# openSX70_ALPHA_V6_5-20181015.net
KiCad netlist of a schematic drawn in EAGLE
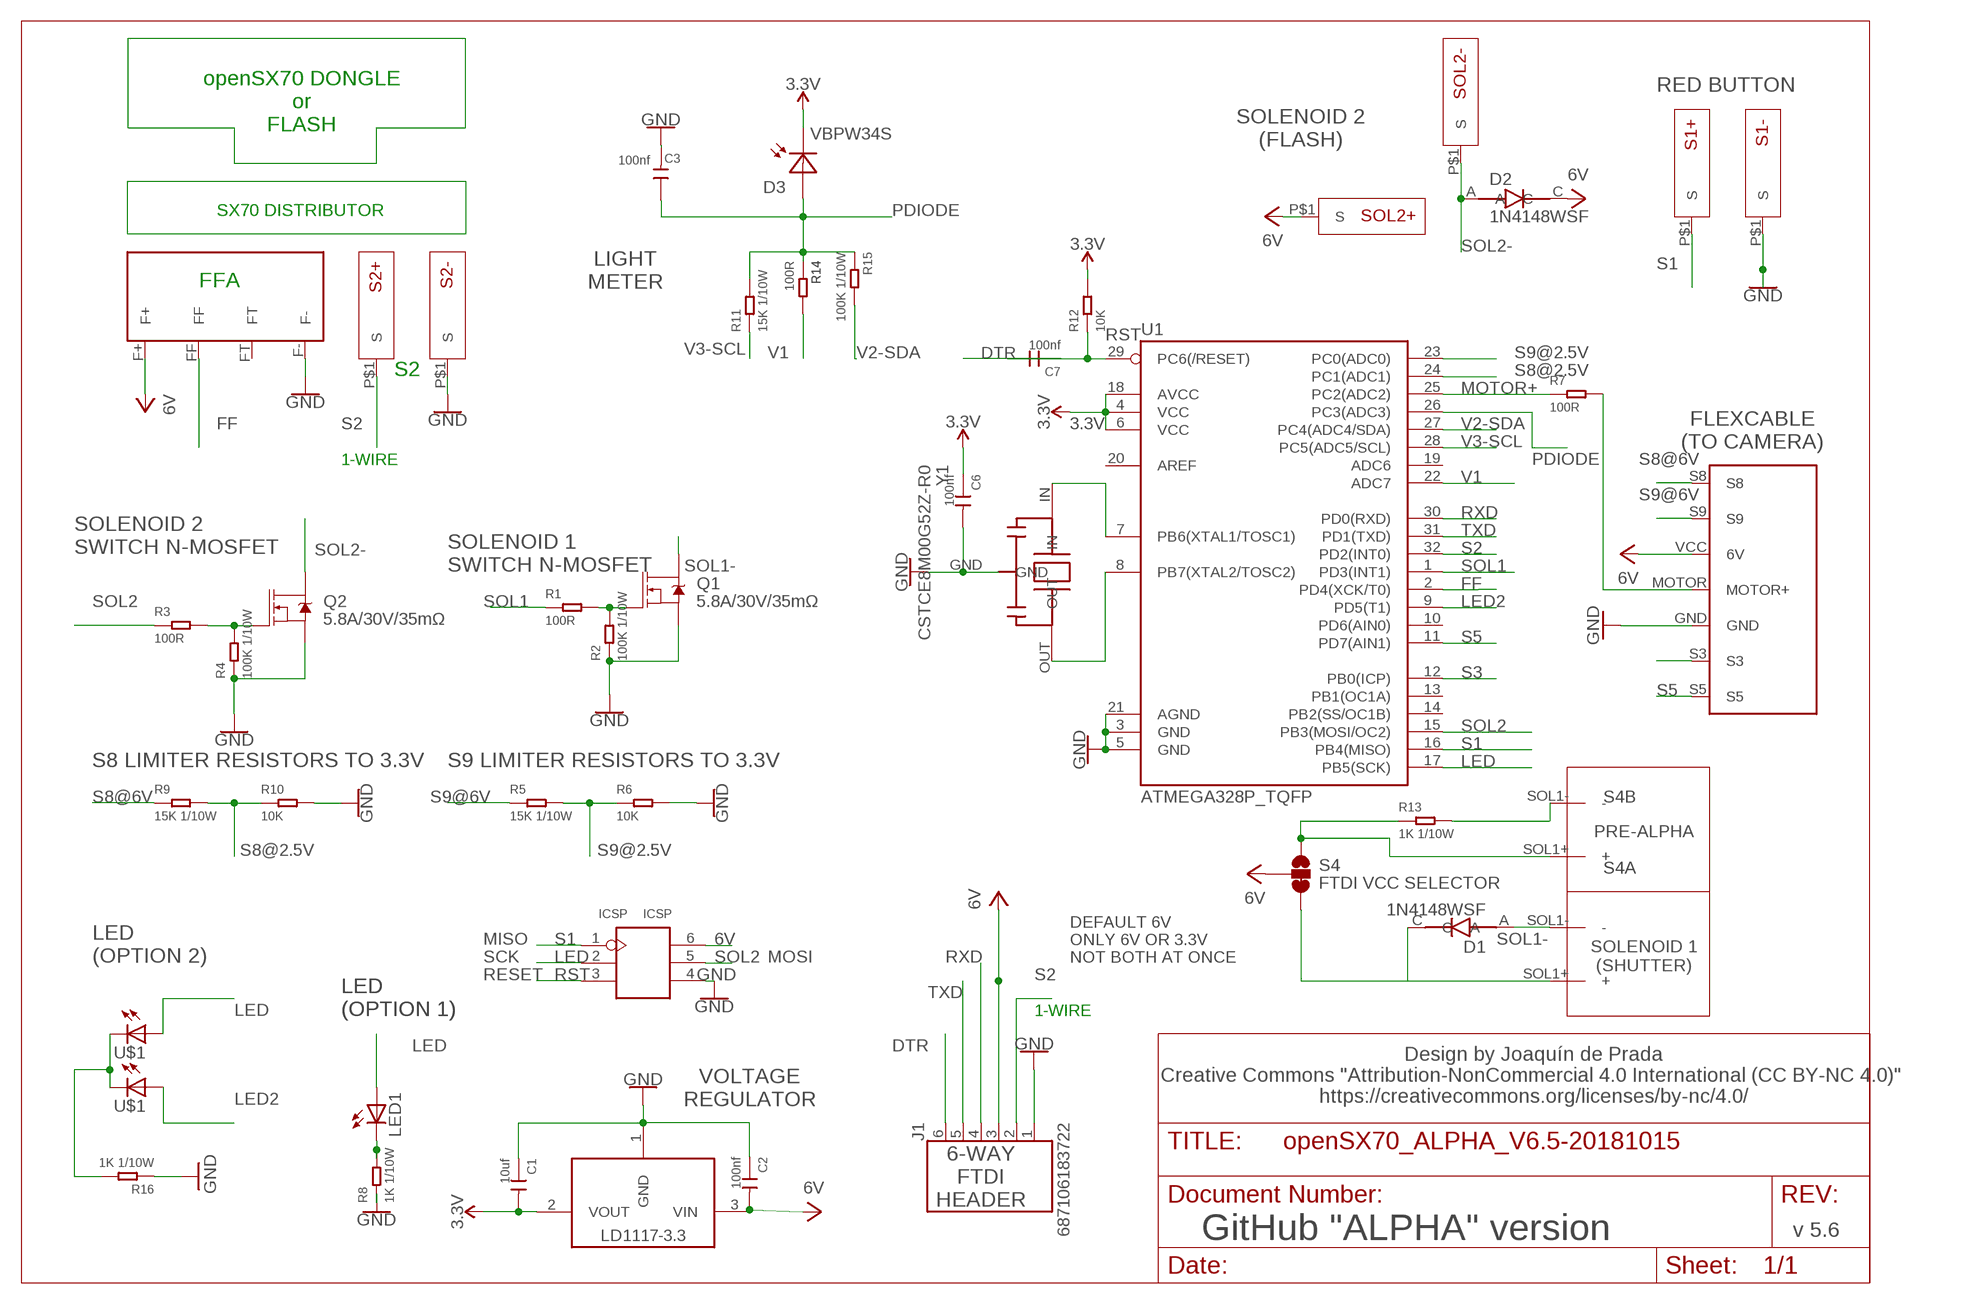
[diagram p0: schematic, sheet 1]

(export (version "E")
  (design (tool "Eeschema 10.0.6"))
  (components
    (comp (ref "C1")
      (value "10uf")
      (footprint "eagle-import:C0603")
      (fields (field (name "MPN") "CC0603KRX5R6BB106"))
      (libsource (lib "eagle-import") (part "CERAMIC-10UF-10V-10%-X5R(0603)"))
    )
    (comp (ref "C2")
      (value "100nf")
      (footprint "eagle-import:C0603")
      (fields (field (name "MPN") "CC0603KRX7R9BB104"))
      (libsource (lib "eagle-import") (part "CERAMIC-100NF-50V-10%-X7R(0603)"))
    )
    (comp (ref "C3")
      (value "100nf")
      (footprint "eagle-import:C0603")
      (fields (field (name "MPN") "CC0603KRX7R9BB104"))
      (libsource (lib "eagle-import") (part "CERAMIC-100NF-50V-10%-X7R(0603)"))
    )
    (comp (ref "C6")
      (value "100nf")
      (footprint "eagle-import:C0603")
      (fields (field (name "MPN") "CC0603KRX7R9BB104"))
      (libsource (lib "eagle-import") (part "CERAMIC-100NF-50V-10%-X7R(0603)"))
    )
    (comp (ref "C7")
      (value "100nf")
      (footprint "eagle-import:C0603")
      (fields (field (name "MPN") "CC0603KRX7R9BB104"))
      (libsource (lib "eagle-import") (part "CERAMIC-100NF-50V-10%-X7R(0603)"))
    )
    (comp (ref "D1")
      (value "1N4148WSF")
      (footprint "eagle-import:SODFL2512X100N")
      (fields (field (name "MANUFACTURER") "Fairchild Semiconductor"))
      (libsource (lib "eagle-import") (part "1N4148WS"))
    )
    (comp (ref "D2")
      (value "1N4148WSF")
      (footprint "eagle-import:SODFL2512X100N")
      (fields (field (name "MANUFACTURER") "Fairchild Semiconductor"))
      (libsource (lib "eagle-import") (part "1N4148WS"))
    )
    (comp (ref "D3")
      (value "VBPW34S")
      (footprint "eagle-import:SOD6439X130N")
      (fields (field (name "DIGI-KEY_PART_NUMBER") "751-1500-1-ND") (field (name "MF") "Vishay"))
      (libsource (lib "eagle-import") (part "VBPW34S"))
    )
    (comp (ref "ICSP")
      (value "ICSP")
      (footprint "eagle-import:H2X3-2.54")
      (libsource (lib "eagle-import") (part "ICSP"))
    )
    (comp (ref "J1")
      (value "687106183722")
      (footprint "eagle-import:687106183722")
      (fields (field (name "MF") "Wurth Electronics"))
      (libsource (lib "eagle-import") (part "687106183722"))
    )
    (comp (ref "LD11172.5V")
      (value "LD1117 2.5V")
      (footprint "eagle-import:SOT223")
      (fields (field (name "MF") "Advanced Monolithic Systems") (field (name "MP") "AMS1117-5.0"))
      (libsource (lib "eagle-import") (part "LD1117-3.3"))
    )
    (comp (ref "LED1")
      (value "LEDCHIPLED_0805")
      (footprint "eagle-import:CHIPLED_0805")
      (libsource (lib "eagle-import") (part "LEDCHIPLED_0805"))
    )
    (comp (ref "Q1")
      (value "5.8A/30V/35mΩ")
      (footprint "eagle-import:SOT23-3")
      (libsource (lib "eagle-import") (part "MOSFET-NCH-AO3404A"))
    )
    (comp (ref "Q2")
      (value "5.8A/30V/35mΩ")
      (footprint "eagle-import:SOT23-3")
      (libsource (lib "eagle-import") (part "MOSFET-NCH-AO3404A"))
    )
    (comp (ref "R1")
      (value "100R")
      (footprint "eagle-import:R0603")
      (fields (field (name "MPN") "RC0603JR-07100RL"))
      (libsource (lib "eagle-import") (part "SMD-RES-100R-5%-1/10W(0603)"))
    )
    (comp (ref "R2")
      (value "100K 1/10W")
      (footprint "eagle-import:R0603")
      (fields (field (name "MPN") "RC0603JR-07100KL"))
      (libsource (lib "eagle-import") (part "SMD-RES-100K-5%-1/10W(0603)"))
    )
    (comp (ref "R3")
      (value "100R")
      (footprint "eagle-import:R0603")
      (fields (field (name "MPN") "RC0603JR-07100RL"))
      (libsource (lib "eagle-import") (part "SMD-RES-100R-5%-1/10W(0603)"))
    )
    (comp (ref "R4")
      (value "100K 1/10W")
      (footprint "eagle-import:R0603")
      (fields (field (name "MPN") "RC0603JR-07100KL"))
      (libsource (lib "eagle-import") (part "SMD-RES-100K-5%-1/10W(0603)"))
    )
    (comp (ref "R5")
      (value "15K 1/10W")
      (footprint "eagle-import:R0603")
      (fields (field (name "MPN") "RC0603FR-0715KL"))
      (libsource (lib "eagle-import") (part "SMD-RES-15K-1%-1/10W(0603)"))
    )
    (comp (ref "R6")
      (value "10K")
      (footprint "eagle-import:R0603")
      (fields (field (name "MPN") "RC0603FR-0710KL"))
      (libsource (lib "eagle-import") (part "SMD-RES-10K-1%-1/10W(0603)"))
    )
    (comp (ref "R7")
      (value "100R")
      (footprint "eagle-import:R0603")
      (fields (field (name "MPN") "RC0603JR-07100RL"))
      (libsource (lib "eagle-import") (part "SMD-RES-100R-5%-1/10W(0603)"))
    )
    (comp (ref "R8")
      (value "1K 1/10W")
      (footprint "eagle-import:R0603")
      (fields (field (name "MPN") "RC0603JR-071KL"))
      (libsource (lib "eagle-import") (part "SMD-RES-1K-5%-1/10W(0603)"))
    )
    (comp (ref "R9")
      (value "15K 1/10W")
      (footprint "eagle-import:R0603")
      (fields (field (name "MPN") "RC0603FR-0715KL"))
      (libsource (lib "eagle-import") (part "SMD-RES-15K-1%-1/10W(0603)"))
    )
    (comp (ref "R10")
      (value "10K")
      (footprint "eagle-import:R0603")
      (fields (field (name "MPN") "RC0603FR-0710KL"))
      (libsource (lib "eagle-import") (part "SMD-RES-10K-1%-1/10W(0603)"))
    )
    (comp (ref "R11")
      (value "15K 1/10W")
      (footprint "eagle-import:R0603")
      (fields (field (name "MPN") "RC0603FR-0715KL"))
      (libsource (lib "eagle-import") (part "SMD-RES-15K-1%-1/10W(0603)"))
    )
    (comp (ref "R12")
      (value "10K")
      (footprint "eagle-import:R0603")
      (fields (field (name "MPN") "RC0603FR-0710KL"))
      (libsource (lib "eagle-import") (part "SMD-RES-10K-1%-1/10W(0603)"))
    )
    (comp (ref "R13")
      (value "1K 1/10W")
      (footprint "eagle-import:R0603")
      (fields (field (name "MPN") "RC0603JR-071KL"))
      (libsource (lib "eagle-import") (part "SMD-RES-1K-5%-1/10W(0603)"))
    )
    (comp (ref "R14")
      (value "100R")
      (footprint "eagle-import:R0603")
      (fields (field (name "MPN") "RC0603JR-07100RL"))
      (libsource (lib "eagle-import") (part "SMD-RES-100R-5%-1/10W(0603)"))
    )
    (comp (ref "R15")
      (value "100K 1/10W")
      (footprint "eagle-import:R0603")
      (fields (field (name "MPN") "RC0603JR-07100KL"))
      (libsource (lib "eagle-import") (part "SMD-RES-100K-5%-1/10W(0603)"))
    )
    (comp (ref "R16")
      (value "1K 1/10W")
      (footprint "eagle-import:R0603")
      (fields (field (name "MPN") "RC0603JR-071KL"))
      (libsource (lib "eagle-import") (part "SMD-RES-1K-5%-1/10W(0603)"))
    )
    (comp (ref "S1+")
      (value "SX70-S-PAD-NEW")
      (footprint "eagle-import:SX70-S-PAD2")
      (libsource (lib "eagle-import") (part "SX70-S-PAD-NEW"))
    )
    (comp (ref "S1-")
      (value "SX70-S-PAD-NEW")
      (footprint "eagle-import:SX70-S-PAD2")
      (libsource (lib "eagle-import") (part "SX70-S-PAD-NEW"))
    )
    (comp (ref "S2+")
      (value "SX70-S-PAD-NEW")
      (footprint "eagle-import:SX70-S-PAD2")
      (libsource (lib "eagle-import") (part "SX70-S-PAD-NEW"))
    )
    (comp (ref "S2-")
      (value "SX70-S-PAD-NEW")
      (footprint "eagle-import:SX70-S-PAD2")
      (libsource (lib "eagle-import") (part "SX70-S-PAD-NEW"))
    )
    (comp (ref "S4")
      (value "FTDI VCC SELECTOR")
      (footprint "eagle-import:SMT-JUMPER_3_1-NC_TRACE_SILK")
      (libsource (lib "eagle-import") (part "JUMPER-SMT_3_1-NC_TRACE_SILK"))
    )
    (comp (ref "SOL1")
      (value "SX70-SOLENOID1-2PADS")
      (footprint "eagle-import:SX70-SOLENOID1-2")
      (libsource (lib "eagle-import") (part "SX70-SOLENOID1-2PADS"))
    )
    (comp (ref "SOL2")
      (value "SX70-SOLENOID1-2PADS")
      (footprint "eagle-import:SX70-SOLENOID1-2")
      (libsource (lib "eagle-import") (part "SX70-SOLENOID1-2PADS"))
    )
    (comp (ref "SOL2+")
      (value "SX70-S-PAD-NEW")
      (footprint "eagle-import:SX70-S-PAD2")
      (libsource (lib "eagle-import") (part "SX70-S-PAD-NEW"))
    )
    (comp (ref "SOL2-")
      (value "SX70-S-PAD-NEW")
      (footprint "eagle-import:SX70-S-PAD2")
      (libsource (lib "eagle-import") (part "SX70-S-PAD-NEW"))
    )
    (comp (ref "U$1")
      (value "DUAL-LED-0603-BIS")
      (footprint "eagle-import:LED_APHB1608SYKSURKC")
      (libsource (lib "eagle-import") (part "DUAL-LED-0603-BIS"))
    )
    (comp (ref "U$2")
      (value "FFA")
      (footprint "eagle-import:FFA-PAD-PACKAGE")
      (libsource (lib "eagle-import") (part "SX70-FFA-PAD"))
    )
    (comp (ref "U$3")
      (value "SX70-7-PAD")
      (footprint "eagle-import:SX70-7-PAD-PROPER")
      (libsource (lib "eagle-import") (part "SX70-7-PAD"))
    )
    (comp (ref "U1")
      (value "ATMEGA328P_TQFP")
      (footprint "eagle-import:TQFP32-08")
      (libsource (lib "eagle-import") (part "ATMEGA328P_TQFP"))
    )
    (comp (ref "Y1")
      (value "CSTCE8M00G52Z-R0")
      (footprint "eagle-import:CFP95P160X100-3N")
      (fields (field (name "MF") "Murata") (field (name "MP") "CSTCE16M0V53-R0"))
      (libsource (lib "eagle-import") (part "CSTCE16M0V53-R0"))
    )
  )
  (nets
    (net (code "1") (name "/DTR") (class "Default")
      (node (ref "C7") (pin "1") (pinfunction "1_1") (pintype "passive"))
      (node (ref "J1") (pin "6") (pinfunction "1_6") (pintype "passive"))
    )
    (net (code "2") (name "/FF") (class "Default")
      (node (ref "U$2") (pin "FF") (pinfunction "FF_FF") (pintype "bidirectional"))
      (node (ref "U1") (pin "2") (pinfunction "PD4(XCK/T0)_2") (pintype "bidirectional"))
    )
    (net (code "3") (name "/LED") (class "Default")
      (node (ref "ICSP") (pin "2") (pinfunction "SCK_2") (pintype "bidirectional"))
      (node (ref "LED1") (pin "A") (pinfunction "A_A") (pintype "passive"))
      (node (ref "U$1") (pin "1") (pinfunction "A_1") (pintype "passive"))
      (node (ref "U1") (pin "17") (pinfunction "PB5(SCK)_17") (pintype "bidirectional"))
    )
    (net (code "4") (name "/LED2") (class "Default")
      (node (ref "U$1") (pin "3") (pinfunction "A1_3") (pintype "passive"))
      (node (ref "U1") (pin "9") (pinfunction "PD5(T1)_9") (pintype "bidirectional"))
    )
    (net (code "5") (name "/MOTOR+") (class "Default")
      (node (ref "R7") (pin "1") (pinfunction "1_1") (pintype "passive"))
      (node (ref "U1") (pin "25") (pinfunction "PC2(ADC2)_25") (pintype "bidirectional"))
    )
    (net (code "6") (name "/PDIODE") (class "Default")
      (node (ref "C3") (pin "1") (pinfunction "1_1") (pintype "passive"))
      (node (ref "D3") (pin "A") (pinfunction "A_A") (pintype "passive"))
      (node (ref "R11") (pin "2") (pinfunction "2_2") (pintype "passive"))
      (node (ref "R14") (pin "1") (pinfunction "1_1") (pintype "passive"))
      (node (ref "R15") (pin "1") (pinfunction "1_1") (pintype "passive"))
      (node (ref "U1") (pin "26") (pinfunction "PC3(ADC3)_26") (pintype "bidirectional"))
    )
    (net (code "7") (name "/RST") (class "Default")
      (node (ref "C7") (pin "2") (pinfunction "2_2") (pintype "passive"))
      (node (ref "ICSP") (pin "3") (pinfunction "RST_3") (pintype "bidirectional"))
      (node (ref "R12") (pin "1") (pinfunction "1_1") (pintype "passive"))
      (node (ref "U1") (pin "29") (pinfunction "PC6(/RESET)_29") (pintype "bidirectional"))
    )
    (net (code "8") (name "/RXD") (class "Default")
      (node (ref "J1") (pin "4") (pinfunction "3_4") (pintype "passive"))
      (node (ref "U1") (pin "30") (pinfunction "PD0(RXD)_30") (pintype "bidirectional"))
    )
    (net (code "9") (name "/S1") (class "Default")
      (node (ref "ICSP") (pin "1") (pinfunction "MISO_1") (pintype "bidirectional"))
      (node (ref "S1+") (pin "P$1") (pinfunction "S_P$1") (pintype "bidirectional"))
      (node (ref "U1") (pin "16") (pinfunction "PB4(MISO)_16") (pintype "bidirectional"))
    )
    (net (code "10") (name "/S2") (class "Default")
      (node (ref "J1") (pin "2") (pinfunction "5_2") (pintype "passive"))
      (node (ref "S2+") (pin "P$1") (pinfunction "S_P$1") (pintype "bidirectional"))
      (node (ref "U1") (pin "32") (pinfunction "PD2(INT0)_32") (pintype "bidirectional"))
    )
    (net (code "11") (name "/S3") (class "Default")
      (node (ref "U$3") (pin "S3") (pinfunction "S3_S3") (pintype "bidirectional"))
      (node (ref "U1") (pin "12") (pinfunction "PB0(ICP)_12") (pintype "bidirectional"))
    )
    (net (code "12") (name "/S5") (class "Default")
      (node (ref "U$3") (pin "S5") (pinfunction "S5_S5") (pintype "bidirectional"))
      (node (ref "U1") (pin "11") (pinfunction "PD7(AIN1)_11") (pintype "bidirectional"))
    )
    (net (code "13") (name "/S8@2.5V") (class "Default")
      (node (ref "R10") (pin "1") (pinfunction "1_1") (pintype "passive"))
      (node (ref "R9") (pin "2") (pinfunction "2_2") (pintype "passive"))
      (node (ref "U1") (pin "24") (pinfunction "PC1(ADC1)_24") (pintype "bidirectional"))
    )
    (net (code "14") (name "/S8@6V") (class "Default")
      (node (ref "R9") (pin "1") (pinfunction "1_1") (pintype "passive"))
      (node (ref "U$3") (pin "S8") (pinfunction "S8_S8") (pintype "bidirectional"))
    )
    (net (code "15") (name "/S9@2.5V") (class "Default")
      (node (ref "R5") (pin "2") (pinfunction "2_2") (pintype "passive"))
      (node (ref "R6") (pin "1") (pinfunction "1_1") (pintype "passive"))
      (node (ref "U1") (pin "23") (pinfunction "PC0(ADC0)_23") (pintype "bidirectional"))
    )
    (net (code "16") (name "/S9@6V") (class "Default")
      (node (ref "R5") (pin "1") (pinfunction "1_1") (pintype "passive"))
      (node (ref "U$3") (pin "S9") (pinfunction "S9_S9") (pintype "bidirectional"))
    )
    (net (code "17") (name "/SOL1") (class "Default")
      (node (ref "R1") (pin "1") (pinfunction "1_1") (pintype "passive"))
      (node (ref "U1") (pin "1") (pinfunction "PD3(INT1)_1") (pintype "bidirectional"))
    )
    (net (code "18") (name "/SOL1-") (class "Default")
      (node (ref "D1") (pin "A") (pinfunction "A_A") (pintype "passive"))
      (node (ref "Q1") (pin "3") (pinfunction "D_3") (pintype "bidirectional"))
      (node (ref "SOL1") (pin "SOL1-") (pinfunction "-_SOL1-") (pintype "bidirectional"))
    )
    (net (code "19") (name "/SOL2") (class "Default")
      (node (ref "ICSP") (pin "5") (pinfunction "MOSI_5") (pintype "bidirectional"))
      (node (ref "R3") (pin "1") (pinfunction "1_1") (pintype "passive"))
      (node (ref "U1") (pin "15") (pinfunction "PB3(MOSI/OC2)_15") (pintype "bidirectional"))
    )
    (net (code "20") (name "/SOL2-") (class "Default")
      (node (ref "D2") (pin "A") (pinfunction "A_A") (pintype "passive"))
      (node (ref "Q2") (pin "3") (pinfunction "D_3") (pintype "bidirectional"))
      (node (ref "SOL2-") (pin "P$1") (pinfunction "S_P$1") (pintype "bidirectional"))
    )
    (net (code "21") (name "/TXD") (class "Default")
      (node (ref "J1") (pin "5") (pinfunction "2_5") (pintype "passive"))
      (node (ref "U1") (pin "31") (pinfunction "PD1(TXD)_31") (pintype "bidirectional"))
    )
    (net (code "22") (name "/V1") (class "Default")
      (node (ref "R14") (pin "2") (pinfunction "2_2") (pintype "passive"))
      (node (ref "U1") (pin "22") (pinfunction "ADC7_22") (pintype "bidirectional"))
    )
    (net (code "23") (name "/V2-SDA") (class "Default")
      (node (ref "R15") (pin "2") (pinfunction "2_2") (pintype "passive"))
      (node (ref "U1") (pin "27") (pinfunction "PC4(ADC4/SDA)_27") (pintype "bidirectional"))
    )
    (net (code "24") (name "/V3-SCL") (class "Default")
      (node (ref "R11") (pin "1") (pinfunction "1_1") (pintype "passive"))
      (node (ref "U1") (pin "28") (pinfunction "PC5(ADC5/SCL)_28") (pintype "bidirectional"))
    )
    (net (code "25") (name "3.3V") (class "Default")
      (node (ref "C1") (pin "2") (pinfunction "2_2") (pintype "passive"))
      (node (ref "C6") (pin "1") (pinfunction "1_1") (pintype "passive"))
      (node (ref "D3") (pin "C") (pinfunction "C_C") (pintype "passive"))
      (node (ref "LD11172.5V") (pin "2") (pinfunction "VOUT_2") (pintype "bidirectional"))
      (node (ref "R12") (pin "2") (pinfunction "2_2") (pintype "passive"))
      (node (ref "U1") (pin "18") (pinfunction "AVCC_18") (pintype "bidirectional"))
      (node (ref "U1") (pin "4") (pinfunction "VCC_4") (pintype "bidirectional"))
      (node (ref "U1") (pin "6") (pinfunction "VCC_6") (pintype "bidirectional"))
    )
    (net (code "26") (name "6V") (class "Default")
      (node (ref "C2") (pin "2") (pinfunction "2_2") (pintype "passive"))
      (node (ref "D2") (pin "C") (pinfunction "C_C") (pintype "passive"))
      (node (ref "ICSP") (pin "6") (pinfunction "VCC_6") (pintype "bidirectional"))
      (node (ref "J1") (pin "3") (pinfunction "4_3") (pintype "passive"))
      (node (ref "LD11172.5V") (pin "3") (pinfunction "VIN_3") (pintype "bidirectional"))
      (node (ref "S4") (pin "2") (pinfunction "2_2") (pintype "passive"))
      (node (ref "SOL2+") (pin "P$1") (pinfunction "S_P$1") (pintype "bidirectional"))
      (node (ref "U$2") (pin "F+") (pinfunction "F+_F+") (pintype "bidirectional"))
      (node (ref "U$3") (pin "VCC") (pinfunction "6V_VCC") (pintype "bidirectional"))
    )
    (net (code "27") (name "GND") (class "Default")
      (node (ref "C1") (pin "1") (pinfunction "1_1") (pintype "passive"))
      (node (ref "C2") (pin "1") (pinfunction "1_1") (pintype "passive"))
      (node (ref "C3") (pin "2") (pinfunction "2_2") (pintype "passive"))
      (node (ref "C6") (pin "2") (pinfunction "2_2") (pintype "passive"))
      (node (ref "ICSP") (pin "4") (pinfunction "GND_4") (pintype "bidirectional"))
      (node (ref "J1") (pin "1") (pinfunction "6_1") (pintype "passive"))
      (node (ref "LD11172.5V") (pin "1") (pinfunction "GND_1") (pintype "bidirectional"))
      (node (ref "Q1") (pin "2") (pinfunction "S_2") (pintype "bidirectional"))
      (node (ref "Q2") (pin "2") (pinfunction "S_2") (pintype "bidirectional"))
      (node (ref "R10") (pin "2") (pinfunction "2_2") (pintype "passive"))
      (node (ref "R16") (pin "1") (pinfunction "1_1") (pintype "passive"))
      (node (ref "R2") (pin "1") (pinfunction "1_1") (pintype "passive"))
      (node (ref "R4") (pin "1") (pinfunction "1_1") (pintype "passive"))
      (node (ref "R6") (pin "2") (pinfunction "2_2") (pintype "passive"))
      (node (ref "R8") (pin "1") (pinfunction "1_1") (pintype "passive"))
      (node (ref "S1-") (pin "P$1") (pinfunction "S_P$1") (pintype "bidirectional"))
      (node (ref "S2-") (pin "P$1") (pinfunction "S_P$1") (pintype "bidirectional"))
      (node (ref "U$2") (pin "F-") (pinfunction "F-_F-") (pintype "bidirectional"))
      (node (ref "U$3") (pin "GND") (pinfunction "GND_GND") (pintype "bidirectional"))
      (node (ref "U1") (pin "21") (pinfunction "AGND_21") (pintype "bidirectional"))
      (node (ref "U1") (pin "3") (pinfunction "GND_3") (pintype "bidirectional"))
      (node (ref "U1") (pin "5") (pinfunction "GND_5") (pintype "bidirectional"))
      (node (ref "Y1") (pin "GND") (pinfunction "GND_GND") (pintype "passive"))
    )
    (net (code "28") (name "Net-(LED1-PadC)") (class "Default")
      (node (ref "LED1") (pin "C") (pinfunction "C_C") (pintype "passive"))
      (node (ref "R8") (pin "2") (pinfunction "2_2") (pintype "passive"))
    )
    (net (code "29") (name "Net-(Q1-G)") (class "Default")
      (node (ref "Q1") (pin "1") (pinfunction "G_1") (pintype "bidirectional"))
      (node (ref "R1") (pin "2") (pinfunction "2_2") (pintype "passive"))
      (node (ref "R2") (pin "2") (pinfunction "2_2") (pintype "passive"))
    )
    (net (code "30") (name "Net-(Q2-G)") (class "Default")
      (node (ref "Q2") (pin "1") (pinfunction "G_1") (pintype "bidirectional"))
      (node (ref "R3") (pin "2") (pinfunction "2_2") (pintype "passive"))
      (node (ref "R4") (pin "2") (pinfunction "2_2") (pintype "passive"))
    )
    (net (code "31") (name "Net-(SOL1-+)") (class "Default")
      (node (ref "D1") (pin "C") (pinfunction "C_C") (pintype "passive"))
      (node (ref "S4") (pin "3") (pinfunction "3_3") (pintype "passive"))
      (node (ref "SOL1") (pin "SOL1+") (pinfunction "+_SOL1+") (pintype "bidirectional"))
    )
    (net (code "32") (name "Net-(SOL2-+)") (class "Default")
      (node (ref "R13") (pin "1") (pinfunction "1_1") (pintype "passive"))
      (node (ref "S4") (pin "1") (pinfunction "1_1") (pintype "passive"))
      (node (ref "SOL2") (pin "SOL1+") (pinfunction "+_SOL1+") (pintype "bidirectional"))
    )
    (net (code "33") (name "Net-(SOL2--)") (class "Default")
      (node (ref "R13") (pin "2") (pinfunction "2_2") (pintype "passive"))
      (node (ref "SOL2") (pin "SOL1-") (pinfunction "-_SOL1-") (pintype "bidirectional"))
    )
    (net (code "34") (name "Net-(U$1-C)") (class "Default")
      (node (ref "R16") (pin "2") (pinfunction "2_2") (pintype "passive"))
      (node (ref "U$1") (pin "2") (pinfunction "C_2") (pintype "passive"))
      (node (ref "U$1") (pin "4") (pinfunction "C1_4") (pintype "passive"))
    )
    (net (code "35") (name "Net-(U$3-MOTOR+)") (class "Default")
      (node (ref "R7") (pin "2") (pinfunction "2_2") (pintype "passive"))
      (node (ref "U$3") (pin "MOTOR") (pinfunction "MOTOR+_MOTOR") (pintype "bidirectional"))
    )
    (net (code "36") (name "Net-(U1-PB6(XTAL1{slash}TOSC1))") (class "Default")
      (node (ref "U1") (pin "7") (pinfunction "PB6(XTAL1/TOSC1)_7") (pintype "bidirectional"))
      (node (ref "Y1") (pin "IN") (pinfunction "IN_IN") (pintype "input"))
    )
    (net (code "37") (name "Net-(U1-PB7(XTAL2{slash}TOSC2))") (class "Default")
      (node (ref "U1") (pin "8") (pinfunction "PB7(XTAL2/TOSC2)_8") (pintype "bidirectional"))
      (node (ref "Y1") (pin "OUT") (pinfunction "OUT_OUT") (pintype "output"))
    )
    (net (code "38") (name "unconnected-(U$2-PadFT)") (class "Default")
      (node (ref "U$2") (pin "FT") (pinfunction "FT_FT") (pintype "bidirectional"))
    )
    (net (code "39") (name "unconnected-(U1-ADC6-Pad19)") (class "Default")
      (node (ref "U1") (pin "19") (pinfunction "ADC6_19") (pintype "bidirectional"))
    )
    (net (code "40") (name "unconnected-(U1-AREF-Pad20)") (class "Default")
      (node (ref "U1") (pin "20") (pinfunction "AREF_20") (pintype "bidirectional"))
    )
    (net (code "41") (name "unconnected-(U1-PB1(OC1A)-Pad13)") (class "Default")
      (node (ref "U1") (pin "13") (pinfunction "PB1(OC1A)_13") (pintype "bidirectional"))
    )
    (net (code "42") (name "unconnected-(U1-PB2(SS{slash}OC1B)-Pad14)") (class "Default")
      (node (ref "U1") (pin "14") (pinfunction "PB2(SS/OC1B)_14") (pintype "bidirectional"))
    )
    (net (code "43") (name "unconnected-(U1-PD6(AIN0)-Pad10)") (class "Default")
      (node (ref "U1") (pin "10") (pinfunction "PD6(AIN0)_10") (pintype "bidirectional"))
    )
  )
)
